# PowerSys.net
KiCad netlist of a schematic drawn in Altium Designer
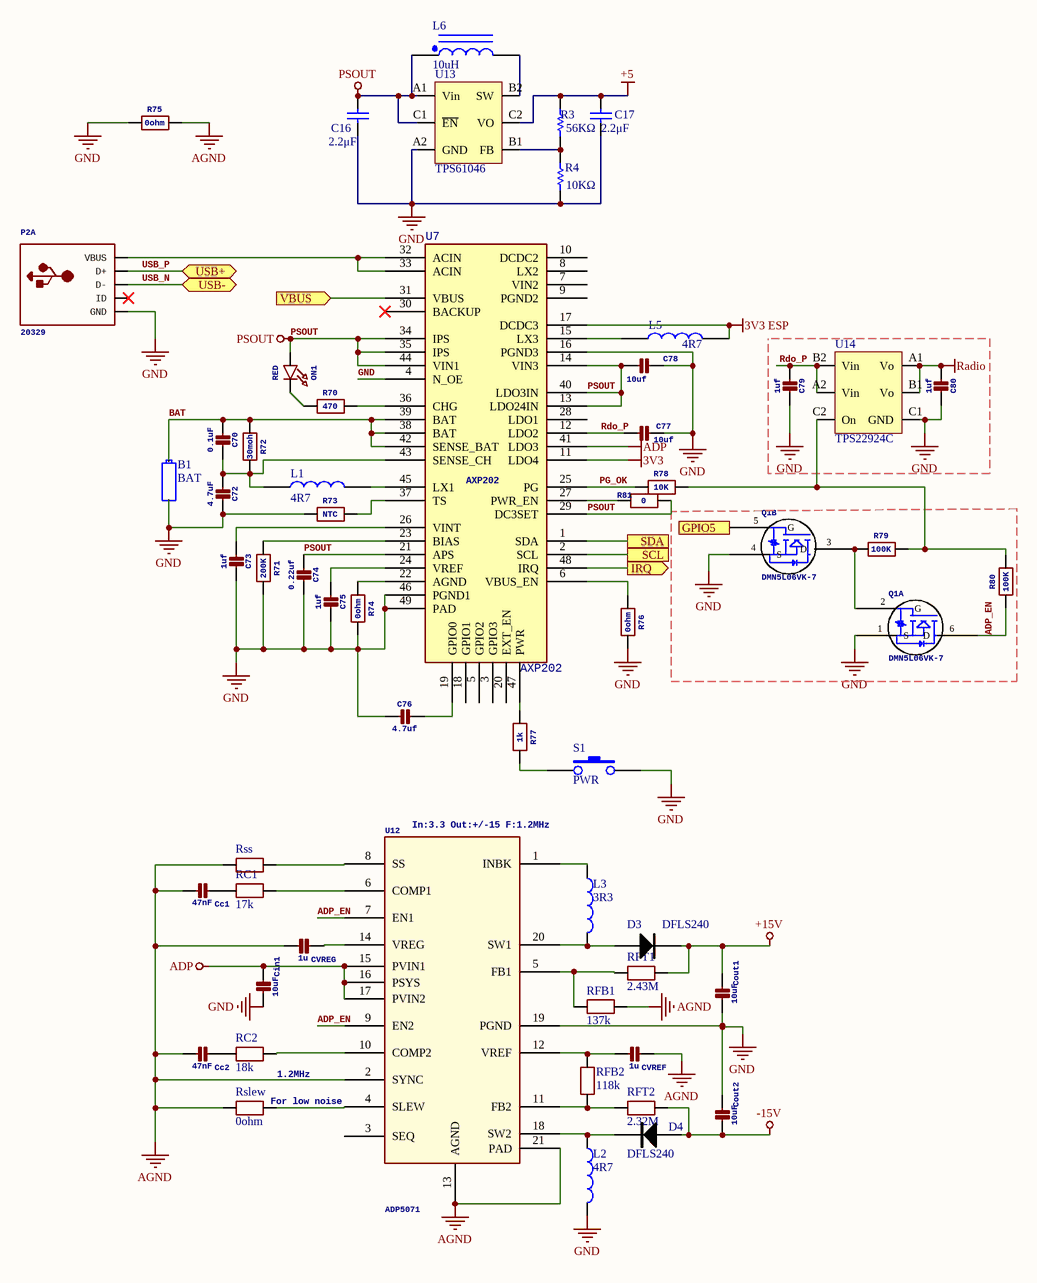
[diagram p0: PowerSys.SchDoc]

(export (version "E")
  (design (tool "Eeschema 10.0.6"))
  (components
    (comp (ref "B1") (value "BAT") (footprint "TJC3-2A") (libsource (lib "Integrated_Library1") (part "BAT")))
    (comp (ref "C16")
      (value "2.2μF")
      (footprint "0603 cap")
      (description "Capacitor")
      (fields (field (name "Comment") "2.2u") (field (name "PUBLISHER") "Altium Limited"))
      (libsource (lib "FTJ") (part "Cap0805"))
    )
    (comp (ref "C17")
      (value "2.2μF")
      (footprint "0603 cap")
      (description "Capacitor")
      (fields (field (name "Comment") "2.2u") (field (name "PUBLISHER") "Altium Limited"))
      (libsource (lib "FTJ") (part "Cap0805"))
    )
    (comp (ref "C70")
      (value "0.1uF")
      (footprint "0603C-GENERIC")
      (libsource (lib "Metro Mini Rev A") (part "CAP_CERAMIC_0805MP"))
    )
    (comp (ref "C72")
      (value "4.7uF")
      (footprint "0603C-GENERIC")
      (libsource (lib "Metro Mini Rev A") (part "CAP_CERAMIC_0805MP"))
    )
    (comp (ref "C73")
      (value "1uf")
      (footprint "0603C-GENERIC")
      (libsource (lib "Metro Mini Rev A") (part "CAP_CERAMIC_0805MP"))
    )
    (comp (ref "C74")
      (value "0.22uf")
      (footprint "0603C-GENERIC")
      (libsource (lib "Metro Mini Rev A") (part "CAP_CERAMIC_0805MP"))
    )
    (comp (ref "C75")
      (value "1uf")
      (footprint "0603C-GENERIC")
      (libsource (lib "Metro Mini Rev A") (part "CAP_CERAMIC_0805MP"))
    )
    (comp (ref "C76")
      (value "4.7uf")
      (footprint "0603C-GENERIC")
      (libsource (lib "") (part "CAP_CERAMIC_0805MP_1"))
    )
    (comp (ref "C77") (value "10uf") (footprint "_0805MP") (libsource (lib "") (part "CAP_CERAMIC_0805MP_1")))
    (comp (ref "C78") (value "10uf") (footprint "_0805MP") (libsource (lib "") (part "CAP_CERAMIC_0805MP_1")))
    (comp (ref "C79")
      (value "1uf")
      (footprint "0201")
      (libsource (lib "Metro Mini Rev A") (part "CAP_CERAMIC_0805MP"))
    )
    (comp (ref "C80")
      (value "1uf")
      (footprint "0201")
      (libsource (lib "Metro Mini Rev A") (part "CAP_CERAMIC_0805MP"))
    )
    (comp (ref "Cc1") (value "47nF") (footprint "0201") (libsource (lib "9G_SCH") (part "CAP")))
    (comp (ref "Cc2") (value "47nF") (footprint "0201") (libsource (lib "9G_SCH") (part "CAP")))
    (comp (ref "Cin1") (value "10uF") (footprint "0805C") (libsource (lib "") (part "CAP_1")))
    (comp (ref "Cout1") (value "10uF") (footprint "0805C") (libsource (lib "") (part "CAP_1")))
    (comp (ref "Cout2") (value "10uF") (footprint "0805C") (libsource (lib "") (part "CAP_1")))
    (comp (ref "CVREF") (value "1u") (footprint "0603AC") (libsource (lib "9G_SCH") (part "CAP")))
    (comp (ref "CVREG") (value "1u") (footprint "0603AC") (libsource (lib "9G_SCH") (part "CAP")))
    (comp (ref "D3")
      (value "DFLS240")
      (footprint "SOD-123")
      (description "DIODE")
      (libsource (lib "MPPT_charger") (part "MBRS140"))
    )
    (comp (ref "D4")
      (value "DFLS240")
      (footprint "SOD-123")
      (description "DIODE")
      (libsource (lib "MPPT_charger") (part "MBRS140"))
    )
    (comp (ref "L1")
      (value "4R7")
      (footprint "SLF6028")
      (libsource (lib "Integrated_Library1") (part "INDUCTOR1"))
    )
    (comp (ref "L2") (value "4R7") (footprint "IHLP2525") (libsource (lib "HardWareSCH") (part "INDUCTOR")))
    (comp (ref "L3") (value "3R3") (footprint "IHLP2525") (libsource (lib "HardWareSCH") (part "INDUCTOR")))
    (comp (ref "L5")
      (value "4R7")
      (footprint "SLF6028")
      (libsource (lib "Integrated_Library1") (part "INDUCTOR1"))
    )
    (comp (ref "L6")
      (value "10uH")
      (footprint "LPS5030")
      (description "Magnetic-Core Inductor with Winding Polarity Marking")
      (fields (field (name "Comment") "6R8") (field (name "PUBLISHER") "Altium Limited"))
      (libsource (lib "FTJ") (part "Inductor Iron Dot"))
    )
    (comp (ref "ON1")
      (value "RED")
      (footprint "CHIPLED_0805_NOOUTLINE")
      (libsource (lib "Metro Mini Rev A") (part "LED0805_NOOUTLINE"))
    )
    (comp (ref "P2")
      (value "20329")
      (footprint "USB MICRO")
      (libsource (lib "Metro Mini Rev A") (part "USB_W_SHIELD_20329"))
    )
    (comp (ref "Q1")
      (value "DMN5L06VK-7")
      (footprint "sot-563")
      (description "DUAL N-CHANNEL ENHANCEMENT MODE MOSFET SOT-563")
      (libsource (lib "9G_SCH") (part "DMN5L06VK-7"))
    )
    (comp (ref "R3")
      (value "56KΩ")
      (footprint "0201")
      (description "Resistor")
      (fields (field (name "Comment") "56K") (field (name "PUBLISHER") "Altium Limited"))
      (libsource (lib "FTJ") (part "RES"))
    )
    (comp (ref "R4")
      (value "10KΩ")
      (footprint "0201")
      (description "Resistor")
      (fields (field (name "Comment") "10K") (field (name "PUBLISHER") "Altium Limited"))
      (libsource (lib "FTJ") (part "RES"))
    )
    (comp (ref "R70")
      (value "470")
      (footprint "0603R-10K")
      (libsource (lib "Metro Mini Rev A") (part "RESISTOR0805_NOOUTLINE"))
    )
    (comp (ref "R71")
      (value "200K")
      (footprint "0603R-10K")
      (libsource (lib "Metro Mini Rev A") (part "RESISTOR0805_NOOUTLINE"))
    )
    (comp (ref "R72")
      (value "30moh")
      (footprint "0603R-10K")
      (libsource (lib "Metro Mini Rev A") (part "RESISTOR0805_NOOUTLINE"))
    )
    (comp (ref "R73")
      (value "NTC")
      (footprint "0603R-10K")
      (libsource (lib "Metro Mini Rev A") (part "RESISTOR0805_NOOUTLINE"))
    )
    (comp (ref "R74")
      (value "0ohm")
      (footprint "0201")
      (libsource (lib "Metro Mini Rev A") (part "RESISTOR0805_NOOUTLINE"))
    )
    (comp (ref "R75")
      (value "0ohm")
      (footprint "0402")
      (libsource (lib "Metro Mini Rev A") (part "RESISTOR0805_NOOUTLINE"))
    )
    (comp (ref "R76")
      (value "0ohm")
      (footprint "0201")
      (libsource (lib "Metro Mini Rev A") (part "RESISTOR0805_NOOUTLINE"))
    )
    (comp (ref "R77")
      (value "1k")
      (footprint "0603R-10K")
      (libsource (lib "Metro Mini Rev A") (part "RESISTOR0805_NOOUTLINE"))
    )
    (comp (ref "R78")
      (value "10K")
      (footprint "0603R-10K")
      (libsource (lib "Metro Mini Rev A") (part "RESISTOR0805_NOOUTLINE"))
    )
    (comp (ref "R79")
      (value "100K")
      (footprint "0201")
      (libsource (lib "Metro Mini Rev A") (part "RESISTOR0805_NOOUTLINE"))
    )
    (comp (ref "R80")
      (value "100K")
      (footprint "0201")
      (libsource (lib "Metro Mini Rev A") (part "RESISTOR0805_NOOUTLINE"))
    )
    (comp (ref "R81")
      (value "0")
      (footprint "0603R-10K")
      (libsource (lib "Metro Mini Rev A") (part "RESISTOR0805_NOOUTLINE"))
    )
    (comp (ref "RC1")
      (value "17k")
      (footprint "0402")
      (description "Resistor")
      (libsource (lib "9G_SCH") (part "RES2"))
    )
    (comp (ref "RC2")
      (value "18k")
      (footprint "0402")
      (description "Resistor")
      (libsource (lib "9G_SCH") (part "RES2"))
    )
    (comp (ref "RFB1")
      (value "137k")
      (footprint "0402")
      (description "Resistor")
      (libsource (lib "9G_SCH") (part "RES2"))
    )
    (comp (ref "RFB2")
      (value "118k")
      (footprint "0402")
      (description "Resistor")
      (libsource (lib "9G_SCH") (part "RES2"))
    )
    (comp (ref "RFT1")
      (value "2.43M")
      (footprint "0402")
      (description "Resistor")
      (libsource (lib "9G_SCH") (part "RES2"))
    )
    (comp (ref "RFT2")
      (value "2.32M")
      (footprint "0402")
      (description "Resistor")
      (libsource (lib "9G_SCH") (part "RES2"))
    )
    (comp (ref "Rslew") (value "0ohm") (footprint "0201") (libsource (lib "9G_SCH") (part "RES2")))
    (comp (ref "Rss")
      (value "~")
      (footprint "0402")
      (description "4 ms (268 kΩ) and 32 ms (50 kΩ)")
      (libsource (lib "9G_SCH") (part "RES2"))
    )
    (comp (ref "S1")
      (value "PWR")
      (footprint "sw_side")
      (libsource (lib "Integrated_Library1") (part "SW-PB"))
    )
    (comp (ref "U7")
      (value "AXP202")
      (footprint "QFN-48-6MM")
      (description "Power system management PWM Charge")
      (libsource (lib "9G_SCH") (part "AXP202"))
    )
    (comp (ref "U12")
      (value "ADP5071")
      (footprint "LFCSP-20")
      (description "2 A/1.2 A DC-to-DC Switching Regulator with\r\nIndependent Positive and Negative Outputs")
      (libsource (lib "9G_SCH") (part "ADP5071"))
    )
    (comp (ref "U13")
      (value "TPS61046")
      (footprint "WCSP-6-DSBGA-6")
      (description "5V Boost")
      (libsource (lib "TI Power Mgt DC-DC Converter") (part "TPS61046"))
    )
    (comp (ref "U14")
      (value "TPS22924C")
      (footprint "WCSP-6-DSBGA-6")
      (description "3.6-V, 2-A, 18.3-mΩ On-Resistance Load Switch")
      (libsource (lib "开关") (part "TPS22924C"))
    )
  )
  (nets
    (net (code "1") (name "+5") (class "Default")
      (node (ref "C17") (pin "2") (pinfunction "2_2") (pintype "passive"))
      (node (ref "R3") (pin "2") (pinfunction "2_2") (pintype "passive"))
      (node (ref "U13") (pin "C2") (pinfunction "VO_C2") (pintype "passive"))
    )
    (net (code "2") (name "+15V") (class "Default")
      (node (ref "Cout1") (pin "1") (pinfunction "1_1") (pintype "passive"))
      (node (ref "D3") (pin "2") (pinfunction "K_2") (pintype "passive"))
      (node (ref "RFT1") (pin "2") (pinfunction "2_2") (pintype "passive"))
    )
    (net (code "3") (name "-15V") (class "Default")
      (node (ref "Cout2") (pin "2") (pinfunction "2_2") (pintype "passive"))
      (node (ref "D4") (pin "1") (pinfunction "A_1") (pintype "passive"))
      (node (ref "RFT2") (pin "2") (pinfunction "2_2") (pintype "passive"))
    )
    (net (code "4") (name "/ADP_EN") (class "Default")
      (node (ref "Q1") (pin "6") (pinfunction "D_6") (pintype "passive"))
      (node (ref "R80") (pin "1") (pinfunction "1_1") (pintype "passive"))
      (node (ref "U12") (pin "7") (pinfunction "EN1_7") (pintype "passive"))
      (node (ref "U12") (pin "9") (pinfunction "EN2_9") (pintype "passive"))
    )
    (net (code "5") (name "/BAT") (class "Default")
      (node (ref "B1") (pin "1") (pinfunction "1_1") (pintype "passive"))
      (node (ref "C70") (pin "2") (pinfunction "2_2") (pintype "passive"))
      (node (ref "R72") (pin "1") (pinfunction "1_1") (pintype "passive"))
      (node (ref "U7") (pin "38") (pinfunction "BAT_38") (pintype "passive"))
      (node (ref "U7") (pin "39") (pinfunction "BAT_39") (pintype "passive"))
      (node (ref "U7") (pin "42") (pinfunction "SENSE_BAT_42") (pintype "passive"))
    )
    (net (code "6") (name "/GPIO5") (class "Default")
      (node (ref "Q1") (pin "5") (pinfunction "G_5") (pintype "passive"))
    )
    (net (code "7") (name "/IRQ") (class "Default")
      (node (ref "U7") (pin "48") (pinfunction "IRQ_48") (pintype "passive"))
    )
    (net (code "8") (name "/PG_OK") (class "Default")
      (node (ref "R78") (pin "1") (pinfunction "1_1") (pintype "passive"))
      (node (ref "U7") (pin "25") (pinfunction "PG_25") (pintype "passive"))
    )
    (net (code "9") (name "/Rdo_P") (class "Default")
      (node (ref "C77") (pin "2") (pinfunction "2_2") (pintype "passive"))
      (node (ref "C79") (pin "2") (pinfunction "2_2") (pintype "passive"))
      (node (ref "U14") (pin "A2") (pinfunction "Vin_A2") (pintype "passive"))
      (node (ref "U14") (pin "B2") (pinfunction "Vin_B2") (pintype "passive"))
      (node (ref "U7") (pin "12") (pinfunction "LDO2_12") (pintype "passive"))
    )
    (net (code "10") (name "/SCL") (class "Default")
      (node (ref "U7") (pin "2") (pinfunction "SCL_2") (pintype "passive"))
    )
    (net (code "11") (name "/SDA") (class "Default")
      (node (ref "U7") (pin "1") (pinfunction "SDA_1") (pintype "passive"))
    )
    (net (code "12") (name "/USB_N") (class "Default")
      (node (ref "P2") (pin "2") (pinfunction "D-_2") (pintype "passive"))
    )
    (net (code "13") (name "/USB_P") (class "Default")
      (node (ref "P2") (pin "3") (pinfunction "D+_3") (pintype "passive"))
    )
    (net (code "14") (name "/VBUS") (class "Default")
      (node (ref "U7") (pin "31") (pinfunction "VBUS_31") (pintype "passive"))
    )
    (net (code "15") (name "3V3") (class "Default")
      (node (ref "U7") (pin "11") (pinfunction "LDO4_11") (pintype "passive"))
    )
    (net (code "16") (name "3V3 ESP") (class "Default")
      (node (ref "L5") (pin "2") (pinfunction "2_2") (pintype "passive"))
      (node (ref "U7") (pin "17") (pinfunction "DCDC3_17") (pintype "passive"))
    )
    (net (code "17") (name "ADP") (class "Default")
      (node (ref "Cin1") (pin "1") (pinfunction "1_1") (pintype "passive"))
      (node (ref "U12") (pin "15") (pinfunction "PVIN1_15") (pintype "passive"))
      (node (ref "U12") (pin "16") (pinfunction "PSYS_16") (pintype "passive"))
      (node (ref "U12") (pin "17") (pinfunction "PVIN2_17") (pintype "passive"))
      (node (ref "U7") (pin "41") (pinfunction "LDO3_41") (pintype "passive"))
    )
    (net (code "18") (name "AGND") (class "Default")
      (node (ref "CVREF") (pin "1") (pinfunction "1_1") (pintype "passive"))
      (node (ref "CVREG") (pin "2") (pinfunction "2_2") (pintype "passive"))
      (node (ref "Cc1") (pin "2") (pinfunction "2_2") (pintype "passive"))
      (node (ref "Cc2") (pin "2") (pinfunction "2_2") (pintype "passive"))
      (node (ref "R75") (pin "2") (pinfunction "2_2") (pintype "passive"))
      (node (ref "RFB1") (pin "1") (pinfunction "1_1") (pintype "passive"))
      (node (ref "Rslew") (pin "2") (pinfunction "2_2") (pintype "passive"))
      (node (ref "Rss") (pin "2") (pinfunction "2_2") (pintype "passive"))
      (node (ref "U12") (pin "13") (pinfunction "AGND_13") (pintype "passive"))
      (node (ref "U12") (pin "2") (pinfunction "SYNC_2") (pintype "passive"))
      (node (ref "U12") (pin "21") (pinfunction "PAD_21") (pintype "passive"))
    )
    (net (code "19") (name "GND") (class "Default")
      (node (ref "B1") (pin "2") (pinfunction "2_2") (pintype "passive"))
      (node (ref "C16") (pin "1") (pinfunction "1_1") (pintype "passive"))
      (node (ref "C17") (pin "1") (pinfunction "1_1") (pintype "passive"))
      (node (ref "C72") (pin "1") (pinfunction "1_1") (pintype "passive"))
      (node (ref "C73") (pin "1") (pinfunction "1_1") (pintype "passive"))
      (node (ref "C74") (pin "1") (pinfunction "1_1") (pintype "passive"))
      (node (ref "C75") (pin "1") (pinfunction "1_1") (pintype "passive"))
      (node (ref "C76") (pin "2") (pinfunction "2_2") (pintype "passive"))
      (node (ref "C77") (pin "1") (pinfunction "1_1") (pintype "passive"))
      (node (ref "C78") (pin "1") (pinfunction "1_1") (pintype "passive"))
      (node (ref "C79") (pin "1") (pinfunction "1_1") (pintype "passive"))
      (node (ref "C80") (pin "1") (pinfunction "1_1") (pintype "passive"))
      (node (ref "Cin1") (pin "2") (pinfunction "2_2") (pintype "passive"))
      (node (ref "Cout1") (pin "2") (pinfunction "2_2") (pintype "passive"))
      (node (ref "Cout2") (pin "1") (pinfunction "1_1") (pintype "passive"))
      (node (ref "L2") (pin "2") (pinfunction "2_2") (pintype "passive"))
      (node (ref "P2") (pin "5") (pinfunction "GND_5") (pintype "power_in"))
      (node (ref "Q1") (pin "1") (pinfunction "S_1") (pintype "passive"))
      (node (ref "Q1") (pin "4") (pinfunction "S_4") (pintype "passive"))
      (node (ref "R4") (pin "1") (pinfunction "1_1") (pintype "passive"))
      (node (ref "R71") (pin "2") (pinfunction "2_2") (pintype "passive"))
      (node (ref "R73") (pin "1") (pinfunction "1_1") (pintype "passive"))
      (node (ref "R74") (pin "2") (pinfunction "2_2") (pintype "passive"))
      (node (ref "R75") (pin "1") (pinfunction "1_1") (pintype "passive"))
      (node (ref "R76") (pin "2") (pinfunction "2_2") (pintype "passive"))
      (node (ref "S1") (pin "1") (pinfunction "2_1") (pintype "passive"))
      (node (ref "U12") (pin "19") (pinfunction "PGND_19") (pintype "passive"))
      (node (ref "U13") (pin "A2") (pinfunction "GND_A2") (pintype "passive"))
      (node (ref "U14") (pin "C1") (pinfunction "GND_C1") (pintype "passive"))
      (node (ref "U7") (pin "16") (pinfunction "PGND3_16") (pintype "passive"))
      (node (ref "U7") (pin "4") (pinfunction "N_OE_4") (pintype "passive"))
      (node (ref "U7") (pin "46") (pinfunction "PGND1_46") (pintype "passive"))
      (node (ref "U7") (pin "49") (pinfunction "PAD_49") (pintype "passive"))
    )
    (net (code "20") (name "Net-(Cc1-Pad1)") (class "Default")
      (node (ref "Cc1") (pin "1") (pinfunction "1_1") (pintype "passive"))
      (node (ref "RC1") (pin "2") (pinfunction "2_2") (pintype "passive"))
    )
    (net (code "21") (name "Net-(Cc2-Pad1)") (class "Default")
      (node (ref "Cc2") (pin "1") (pinfunction "1_1") (pintype "passive"))
      (node (ref "RC2") (pin "2") (pinfunction "2_2") (pintype "passive"))
    )
    (net (code "22") (name "Net-(D3-A)") (class "Default")
      (node (ref "D3") (pin "1") (pinfunction "A_1") (pintype "passive"))
      (node (ref "L3") (pin "2") (pinfunction "2_2") (pintype "passive"))
      (node (ref "U12") (pin "20") (pinfunction "SW1_20") (pintype "passive"))
    )
    (net (code "23") (name "Net-(D4-K)") (class "Default")
      (node (ref "D4") (pin "2") (pinfunction "K_2") (pintype "passive"))
      (node (ref "L2") (pin "1") (pinfunction "1_1") (pintype "passive"))
      (node (ref "U12") (pin "18") (pinfunction "SW2_18") (pintype "passive"))
    )
    (net (code "24") (name "Net-(ON1-PadC)") (class "Default")
      (node (ref "ON1") (pin "C") (pinfunction "C_C") (pintype "passive"))
      (node (ref "R70") (pin "1") (pinfunction "1_1") (pintype "passive"))
    )
    (net (code "25") (name "Net-(P2A-VBUS)") (class "Default")
      (node (ref "P2") (pin "1") (pinfunction "VBUS_1") (pintype "power_in"))
      (node (ref "U7") (pin "32") (pinfunction "ACIN_32") (pintype "passive"))
      (node (ref "U7") (pin "33") (pinfunction "ACIN_33") (pintype "passive"))
    )
    (net (code "26") (name "Net-(Q1A-G)") (class "Default")
      (node (ref "Q1") (pin "2") (pinfunction "G_2") (pintype "passive"))
      (node (ref "Q1") (pin "3") (pinfunction "D_3") (pintype "passive"))
      (node (ref "R79") (pin "1") (pinfunction "1_1") (pintype "passive"))
    )
    (net (code "27") (name "Net-(S1-1)") (class "Default")
      (node (ref "R77") (pin "2") (pinfunction "2_2") (pintype "passive"))
      (node (ref "S1") (pin "2") (pinfunction "1_2") (pintype "passive"))
    )
    (net (code "28") (name "Net-(U7-AGND)") (class "Default")
      (node (ref "R74") (pin "1") (pinfunction "1_1") (pintype "passive"))
      (node (ref "U7") (pin "22") (pinfunction "AGND_22") (pintype "passive"))
    )
    (net (code "29") (name "Net-(U7-BIAS)") (class "Default")
      (node (ref "R71") (pin "1") (pinfunction "1_1") (pintype "passive"))
      (node (ref "U7") (pin "23") (pinfunction "BIAS_23") (pintype "passive"))
    )
    (net (code "30") (name "Net-(U7-CHG)") (class "Default")
      (node (ref "R70") (pin "2") (pinfunction "2_2") (pintype "passive"))
      (node (ref "U7") (pin "36") (pinfunction "CHG_36") (pintype "passive"))
    )
    (net (code "31") (name "Net-(U7-GPIO0)") (class "Default")
      (node (ref "C76") (pin "1") (pinfunction "1_1") (pintype "passive"))
      (node (ref "U7") (pin "19") (pinfunction "GPIO0_19") (pintype "passive"))
    )
    (net (code "32") (name "Net-(U7-LX1)") (class "Default")
      (node (ref "L1") (pin "2") (pinfunction "2_2") (pintype "passive"))
      (node (ref "U7") (pin "45") (pinfunction "LX1_45") (pintype "passive"))
    )
    (net (code "33") (name "Net-(U7-LX3)") (class "Default")
      (node (ref "L5") (pin "1") (pinfunction "1_1") (pintype "passive"))
      (node (ref "U7") (pin "15") (pinfunction "LX3_15") (pintype "passive"))
    )
    (net (code "34") (name "Net-(U7-PWR)") (class "Default")
      (node (ref "R77") (pin "1") (pinfunction "1_1") (pintype "passive"))
      (node (ref "U7") (pin "47") (pinfunction "PWR_47") (pintype "passive"))
    )
    (net (code "35") (name "Net-(U7-PWR_EN)") (class "Default")
      (node (ref "R81") (pin "1") (pinfunction "1_1") (pintype "passive"))
      (node (ref "U7") (pin "27") (pinfunction "PWR_EN_27") (pintype "passive"))
    )
    (net (code "36") (name "Net-(U7-SENSE_CH)") (class "Default")
      (node (ref "C70") (pin "1") (pinfunction "1_1") (pintype "passive"))
      (node (ref "C72") (pin "2") (pinfunction "2_2") (pintype "passive"))
      (node (ref "L1") (pin "1") (pinfunction "1_1") (pintype "passive"))
      (node (ref "R72") (pin "2") (pinfunction "2_2") (pintype "passive"))
      (node (ref "U7") (pin "43") (pinfunction "SENSE_CH_43") (pintype "passive"))
    )
    (net (code "37") (name "Net-(U7-TS)") (class "Default")
      (node (ref "R73") (pin "2") (pinfunction "2_2") (pintype "passive"))
      (node (ref "U7") (pin "37") (pinfunction "TS_37") (pintype "passive"))
    )
    (net (code "38") (name "Net-(U7-VBUS_EN)") (class "Default")
      (node (ref "R76") (pin "1") (pinfunction "1_1") (pintype "passive"))
      (node (ref "U7") (pin "6") (pinfunction "VBUS_EN_6") (pintype "passive"))
    )
    (net (code "39") (name "Net-(U7-VINT)") (class "Default")
      (node (ref "C73") (pin "2") (pinfunction "2_2") (pintype "passive"))
      (node (ref "U7") (pin "26") (pinfunction "VINT_26") (pintype "passive"))
    )
    (net (code "40") (name "Net-(U7-VREF)") (class "Default")
      (node (ref "C75") (pin "2") (pinfunction "2_2") (pintype "passive"))
      (node (ref "U7") (pin "24") (pinfunction "VREF_24") (pintype "passive"))
    )
    (net (code "41") (name "Net-(U12-COMP1)") (class "Default")
      (node (ref "RC1") (pin "1") (pinfunction "1_1") (pintype "passive"))
      (node (ref "U12") (pin "6") (pinfunction "COMP1_6") (pintype "passive"))
    )
    (net (code "42") (name "Net-(U12-COMP2)") (class "Default")
      (node (ref "RC2") (pin "1") (pinfunction "1_1") (pintype "passive"))
      (node (ref "U12") (pin "10") (pinfunction "COMP2_10") (pintype "passive"))
    )
    (net (code "43") (name "Net-(U12-FB1)") (class "Default")
      (node (ref "RFB1") (pin "2") (pinfunction "2_2") (pintype "passive"))
      (node (ref "RFT1") (pin "1") (pinfunction "1_1") (pintype "passive"))
      (node (ref "U12") (pin "5") (pinfunction "FB1_5") (pintype "passive"))
    )
    (net (code "44") (name "Net-(U12-FB2)") (class "Default")
      (node (ref "RFB2") (pin "2") (pinfunction "2_2") (pintype "passive"))
      (node (ref "RFT2") (pin "1") (pinfunction "1_1") (pintype "passive"))
      (node (ref "U12") (pin "11") (pinfunction "FB2_11") (pintype "passive"))
    )
    (net (code "45") (name "Net-(U12-INBK)") (class "Default")
      (node (ref "L3") (pin "1") (pinfunction "1_1") (pintype "passive"))
      (node (ref "U12") (pin "1") (pinfunction "INBK_1") (pintype "passive"))
    )
    (net (code "46") (name "Net-(U12-SLEW)") (class "Default")
      (node (ref "Rslew") (pin "1") (pinfunction "1_1") (pintype "passive"))
      (node (ref "U12") (pin "4") (pinfunction "SLEW_4") (pintype "passive"))
    )
    (net (code "47") (name "Net-(U12-SS)") (class "Default")
      (node (ref "Rss") (pin "1") (pinfunction "1_1") (pintype "passive"))
      (node (ref "U12") (pin "8") (pinfunction "SS_8") (pintype "passive"))
    )
    (net (code "48") (name "Net-(U12-VREF)") (class "Default")
      (node (ref "CVREF") (pin "2") (pinfunction "2_2") (pintype "passive"))
      (node (ref "RFB2") (pin "1") (pinfunction "1_1") (pintype "passive"))
      (node (ref "U12") (pin "12") (pinfunction "VREF_12") (pintype "passive"))
    )
    (net (code "49") (name "Net-(U12-VREG)") (class "Default")
      (node (ref "CVREG") (pin "1") (pinfunction "1_1") (pintype "passive"))
      (node (ref "U12") (pin "14") (pinfunction "VREG_14") (pintype "passive"))
    )
    (net (code "50") (name "Net-(U13-FB)") (class "Default")
      (node (ref "R3") (pin "1") (pinfunction "1_1") (pintype "passive"))
      (node (ref "R4") (pin "2") (pinfunction "2_2") (pintype "passive"))
      (node (ref "U13") (pin "B1") (pinfunction "FB_B1") (pintype "passive"))
    )
    (net (code "51") (name "Net-(U13-SW)") (class "Default")
      (node (ref "L6") (pin "2") (pinfunction "2_2") (pintype "passive"))
      (node (ref "U13") (pin "B2") (pinfunction "SW_B2") (pintype "passive"))
    )
    (net (code "52") (name "Net-(U14-On)") (class "Default")
      (node (ref "R78") (pin "2") (pinfunction "2_2") (pintype "passive"))
      (node (ref "R79") (pin "2") (pinfunction "2_2") (pintype "passive"))
      (node (ref "R80") (pin "2") (pinfunction "2_2") (pintype "passive"))
      (node (ref "U14") (pin "C2") (pinfunction "On_C2") (pintype "passive"))
    )
    (net (code "53") (name "PSOUT") (class "Default")
      (node (ref "C16") (pin "2") (pinfunction "2_2") (pintype "passive"))
      (node (ref "C74") (pin "2") (pinfunction "2_2") (pintype "passive"))
      (node (ref "C78") (pin "2") (pinfunction "2_2") (pintype "passive"))
      (node (ref "L6") (pin "1") (pinfunction "1_1") (pintype "passive"))
      (node (ref "ON1") (pin "A") (pinfunction "A_A") (pintype "passive"))
      (node (ref "R81") (pin "2") (pinfunction "2_2") (pintype "passive"))
      (node (ref "U13") (pin "A1") (pinfunction "Vin_A1") (pintype "passive"))
      (node (ref "U13") (pin "C1") (pinfunction "~{EN}_C1") (pintype "passive"))
      (node (ref "U7") (pin "13") (pinfunction "LDO24IN_13") (pintype "passive"))
      (node (ref "U7") (pin "14") (pinfunction "VIN3_14") (pintype "passive"))
      (node (ref "U7") (pin "21") (pinfunction "APS_21") (pintype "passive"))
      (node (ref "U7") (pin "29") (pinfunction "DC3SET_29") (pintype "passive"))
      (node (ref "U7") (pin "34") (pinfunction "IPS_34") (pintype "passive"))
      (node (ref "U7") (pin "35") (pinfunction "IPS_35") (pintype "passive"))
      (node (ref "U7") (pin "40") (pinfunction "LDO3IN_40") (pintype "passive"))
      (node (ref "U7") (pin "44") (pinfunction "VIN1_44") (pintype "passive"))
    )
    (net (code "54") (name "Radio") (class "Default")
      (node (ref "C80") (pin "2") (pinfunction "2_2") (pintype "passive"))
      (node (ref "U14") (pin "A1") (pinfunction "Vo_A1") (pintype "passive"))
      (node (ref "U14") (pin "B1") (pinfunction "Vo_B1") (pintype "passive"))
    )
    (net (code "55") (name "unconnected-(P2A-ID-Pad4)") (class "Default")
      (node (ref "P2") (pin "4") (pinfunction "ID_4") (pintype "passive+no_connect"))
    )
    (net (code "56") (name "unconnected-(U7-BACKUP-Pad30)") (class "Default")
      (node (ref "U7") (pin "30") (pinfunction "BACKUP_30") (pintype "passive+no_connect"))
    )
    (net (code "57") (name "unconnected-(U7-DCDC2-Pad10)") (class "Default")
      (node (ref "U7") (pin "10") (pinfunction "DCDC2_10") (pintype "passive"))
    )
    (net (code "58") (name "unconnected-(U7-EXT_EN-Pad20)") (class "Default")
      (node (ref "U7") (pin "20") (pinfunction "EXT_EN_20") (pintype "passive"))
    )
    (net (code "59") (name "unconnected-(U7-GPIO1-Pad18)") (class "Default")
      (node (ref "U7") (pin "18") (pinfunction "GPIO1_18") (pintype "passive"))
    )
    (net (code "60") (name "unconnected-(U7-GPIO2-Pad5)") (class "Default")
      (node (ref "U7") (pin "5") (pinfunction "GPIO2_5") (pintype "passive"))
    )
    (net (code "61") (name "unconnected-(U7-GPIO3-Pad3)") (class "Default")
      (node (ref "U7") (pin "3") (pinfunction "GPIO3_3") (pintype "passive"))
    )
    (net (code "62") (name "unconnected-(U7-LDO1-Pad28)") (class "Default")
      (node (ref "U7") (pin "28") (pinfunction "LDO1_28") (pintype "passive"))
    )
    (net (code "63") (name "unconnected-(U7-LX2-Pad8)") (class "Default")
      (node (ref "U7") (pin "8") (pinfunction "LX2_8") (pintype "passive"))
    )
    (net (code "64") (name "unconnected-(U7-PGND2-Pad9)") (class "Default")
      (node (ref "U7") (pin "9") (pinfunction "PGND2_9") (pintype "passive"))
    )
    (net (code "65") (name "unconnected-(U7-VIN2-Pad7)") (class "Default")
      (node (ref "U7") (pin "7") (pinfunction "VIN2_7") (pintype "passive"))
    )
    (net (code "66") (name "unconnected-(U12-SEQ-Pad3)") (class "Default")
      (node (ref "U12") (pin "3") (pinfunction "SEQ_3") (pintype "passive"))
    )
  )
)
